# motor.net
KiCad netlist of a schematic drawn in EAGLE
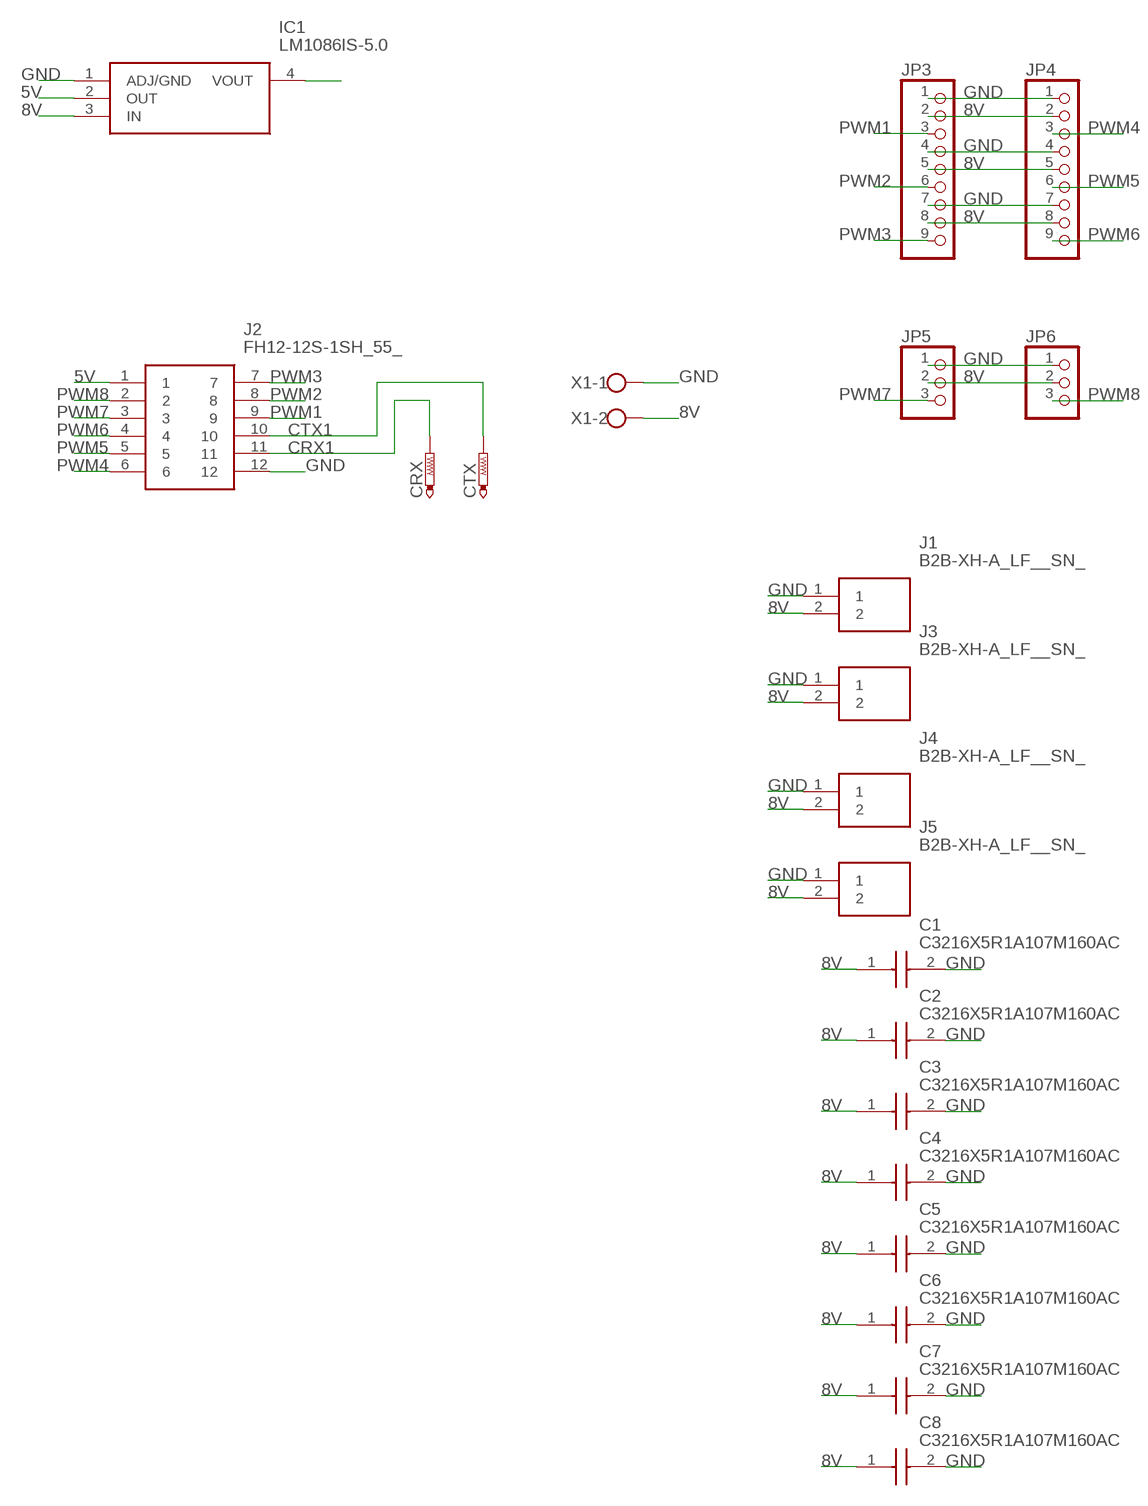
[diagram p0: schematic, sheet 1]

(export (version "E")
  (design (tool "Eeschema 10.0.6"))
  (components
    (comp (ref "C1")
      (value "C3216X5R1A107M160AC")
      (footprint "eagle-import:CAPC3216X180N")
      (fields (field (name "MOUSER_PART_NUMBER") "810-C3216X5R1A107M"))
      (libsource (lib "eagle-import") (part "C3216X5R1A107M160AC"))
    )
    (comp (ref "C2")
      (value "C3216X5R1A107M160AC")
      (footprint "eagle-import:CAPC3216X180N")
      (fields (field (name "MOUSER_PART_NUMBER") "810-C3216X5R1A107M"))
      (libsource (lib "eagle-import") (part "C3216X5R1A107M160AC"))
    )
    (comp (ref "C3")
      (value "C3216X5R1A107M160AC")
      (footprint "eagle-import:CAPC3216X180N")
      (fields (field (name "MOUSER_PART_NUMBER") "810-C3216X5R1A107M"))
      (libsource (lib "eagle-import") (part "C3216X5R1A107M160AC"))
    )
    (comp (ref "C4")
      (value "C3216X5R1A107M160AC")
      (footprint "eagle-import:CAPC3216X180N")
      (fields (field (name "MOUSER_PART_NUMBER") "810-C3216X5R1A107M"))
      (libsource (lib "eagle-import") (part "C3216X5R1A107M160AC"))
    )
    (comp (ref "C5")
      (value "C3216X5R1A107M160AC")
      (footprint "eagle-import:CAPC3216X180N")
      (fields (field (name "MOUSER_PART_NUMBER") "810-C3216X5R1A107M"))
      (libsource (lib "eagle-import") (part "C3216X5R1A107M160AC"))
    )
    (comp (ref "C6")
      (value "C3216X5R1A107M160AC")
      (footprint "eagle-import:CAPC3216X180N")
      (fields (field (name "MOUSER_PART_NUMBER") "810-C3216X5R1A107M"))
      (libsource (lib "eagle-import") (part "C3216X5R1A107M160AC"))
    )
    (comp (ref "C7")
      (value "C3216X5R1A107M160AC")
      (footprint "eagle-import:CAPC3216X180N")
      (fields (field (name "MOUSER_PART_NUMBER") "810-C3216X5R1A107M"))
      (libsource (lib "eagle-import") (part "C3216X5R1A107M160AC"))
    )
    (comp (ref "C8")
      (value "C3216X5R1A107M160AC")
      (footprint "eagle-import:CAPC3216X180N")
      (fields (field (name "MOUSER_PART_NUMBER") "810-C3216X5R1A107M"))
      (libsource (lib "eagle-import") (part "C3216X5R1A107M160AC"))
    )
    (comp (ref "CRX")
      (value "PTR1TP20R")
      (footprint "eagle-import:TP20R")
      (libsource (lib "eagle-import") (part "PTR1TP20R"))
    )
    (comp (ref "CTX")
      (value "PTR1TP20SQ")
      (footprint "eagle-import:TP20SQ")
      (libsource (lib "eagle-import") (part "PTR1TP20SQ"))
    )
    (comp (ref "IC1")
      (value "LM1086IS-5.0")
      (footprint "eagle-import:TO254P1435X457-4N")
      (fields (field (name "MOUSER_PART_NUMBER") "926-LM1086IS-50"))
      (libsource (lib "eagle-import") (part "LM1086IS-5.0"))
    )
    (comp (ref "J1")
      (value "B2B-XH-A_LF__SN_")
      (footprint "eagle-import:SHDR2W64P0X250_1X2_740X575X700")
      (fields
        (field (name "MANUFACTURER_PART_NUMBER") "B2B-XH-A(LF)(SN)")
        (field (name "RS_PART_NUMBER") "8201554P")
      )
      (libsource (lib "eagle-import") (part "B2B-XH-A_LF__SN_"))
    )
    (comp (ref "J2")
      (value "FH12-12S-1SH_55_")
      (footprint "eagle-import:FH12-12S-1SH(55)")
      (fields
        (field (name "MANUFACTURER_PART_NUMBER") "FH12-12S-1SH(55)")
        (field (name "MOUSER_PART_NUMBER") "798-FH1212S1SH55")
      )
      (libsource (lib "eagle-import") (part "FH12-12S-1SH_55_"))
    )
    (comp (ref "J3")
      (value "B2B-XH-A_LF__SN_")
      (footprint "eagle-import:SHDR2W64P0X250_1X2_740X575X700")
      (fields
        (field (name "MANUFACTURER_PART_NUMBER") "B2B-XH-A(LF)(SN)")
        (field (name "RS_PART_NUMBER") "8201554P")
      )
      (libsource (lib "eagle-import") (part "B2B-XH-A_LF__SN_"))
    )
    (comp (ref "J4")
      (value "B2B-XH-A_LF__SN_")
      (footprint "eagle-import:SHDR2W64P0X250_1X2_740X575X700")
      (fields
        (field (name "MANUFACTURER_PART_NUMBER") "B2B-XH-A(LF)(SN)")
        (field (name "RS_PART_NUMBER") "8201554P")
      )
      (libsource (lib "eagle-import") (part "B2B-XH-A_LF__SN_"))
    )
    (comp (ref "J5")
      (value "B2B-XH-A_LF__SN_")
      (footprint "eagle-import:SHDR2W64P0X250_1X2_740X575X700")
      (fields
        (field (name "MANUFACTURER_PART_NUMBER") "B2B-XH-A(LF)(SN)")
        (field (name "RS_PART_NUMBER") "8201554P")
      )
      (libsource (lib "eagle-import") (part "B2B-XH-A_LF__SN_"))
    )
    (comp (ref "JP3")
      (value "PINHD-1X9")
      (footprint "eagle-import:1X09")
      (libsource (lib "eagle-import") (part "PINHD-1X9"))
    )
    (comp (ref "JP4")
      (value "PINHD-1X9")
      (footprint "eagle-import:1X09")
      (libsource (lib "eagle-import") (part "PINHD-1X9"))
    )
    (comp (ref "JP5")
      (value "PINHD-1X3")
      (footprint "eagle-import:1X03")
      (libsource (lib "eagle-import") (part "PINHD-1X3"))
    )
    (comp (ref "JP6")
      (value "PINHD-1X3")
      (footprint "eagle-import:1X03")
      (libsource (lib "eagle-import") (part "PINHD-1X3"))
    )
    (comp (ref "X1")
      (value "W237-102")
      (footprint "eagle-import:W237-102")
      (fields (field (name "MPN") "237-102"))
      (libsource (lib "eagle-import") (part "W237-102"))
    )
  )
  (nets
    (net (code "1") (name "/5V") (class "Default")
      (node (ref "IC1") (pin "2") (pinfunction "OUT_2") (pintype "bidirectional"))
      (node (ref "J2") (pin "1") (pinfunction "1_1") (pintype "bidirectional"))
    )
    (net (code "2") (name "/8V") (class "Default")
      (node (ref "C1") (pin "1") (pinfunction "1_1") (pintype "bidirectional"))
      (node (ref "C2") (pin "1") (pinfunction "1_1") (pintype "bidirectional"))
      (node (ref "C3") (pin "1") (pinfunction "1_1") (pintype "bidirectional"))
      (node (ref "C4") (pin "1") (pinfunction "1_1") (pintype "bidirectional"))
      (node (ref "C5") (pin "1") (pinfunction "1_1") (pintype "bidirectional"))
      (node (ref "C6") (pin "1") (pinfunction "1_1") (pintype "bidirectional"))
      (node (ref "C7") (pin "1") (pinfunction "1_1") (pintype "bidirectional"))
      (node (ref "C8") (pin "1") (pinfunction "1_1") (pintype "bidirectional"))
      (node (ref "IC1") (pin "3") (pinfunction "IN_3") (pintype "bidirectional"))
      (node (ref "J1") (pin "2") (pinfunction "2_2") (pintype "bidirectional"))
      (node (ref "J3") (pin "2") (pinfunction "2_2") (pintype "bidirectional"))
      (node (ref "J4") (pin "2") (pinfunction "2_2") (pintype "bidirectional"))
      (node (ref "J5") (pin "2") (pinfunction "2_2") (pintype "bidirectional"))
      (node (ref "JP3") (pin "2") (pinfunction "2_2") (pintype "passive"))
      (node (ref "JP3") (pin "5") (pinfunction "5_5") (pintype "passive"))
      (node (ref "JP3") (pin "8") (pinfunction "8_8") (pintype "passive"))
      (node (ref "JP4") (pin "2") (pinfunction "2_2") (pintype "passive"))
      (node (ref "JP4") (pin "5") (pinfunction "5_5") (pintype "passive"))
      (node (ref "JP4") (pin "8") (pinfunction "8_8") (pintype "passive"))
      (node (ref "JP5") (pin "2") (pinfunction "2_2") (pintype "passive"))
      (node (ref "JP6") (pin "2") (pinfunction "2_2") (pintype "passive"))
      (node (ref "X1") (pin "2") (pinfunction "KL_2") (pintype "passive"))
    )
    (net (code "3") (name "/CRX1") (class "Default")
      (node (ref "CRX") (pin "TP") (pinfunction "TP_TP") (pintype "input"))
      (node (ref "J2") (pin "11") (pinfunction "11_11") (pintype "bidirectional"))
    )
    (net (code "4") (name "/CTX1") (class "Default")
      (node (ref "CTX") (pin "TP") (pinfunction "TP_TP") (pintype "input"))
      (node (ref "J2") (pin "10") (pinfunction "10_10") (pintype "bidirectional"))
    )
    (net (code "5") (name "/GND") (class "Default")
      (node (ref "C1") (pin "2") (pinfunction "2_2") (pintype "bidirectional"))
      (node (ref "C2") (pin "2") (pinfunction "2_2") (pintype "bidirectional"))
      (node (ref "C3") (pin "2") (pinfunction "2_2") (pintype "bidirectional"))
      (node (ref "C4") (pin "2") (pinfunction "2_2") (pintype "bidirectional"))
      (node (ref "C5") (pin "2") (pinfunction "2_2") (pintype "bidirectional"))
      (node (ref "C6") (pin "2") (pinfunction "2_2") (pintype "bidirectional"))
      (node (ref "C7") (pin "2") (pinfunction "2_2") (pintype "bidirectional"))
      (node (ref "C8") (pin "2") (pinfunction "2_2") (pintype "bidirectional"))
      (node (ref "IC1") (pin "1") (pinfunction "ADJ/GND_1") (pintype "bidirectional"))
      (node (ref "J1") (pin "1") (pinfunction "1_1") (pintype "bidirectional"))
      (node (ref "J2") (pin "12") (pinfunction "12_12") (pintype "bidirectional"))
      (node (ref "J3") (pin "1") (pinfunction "1_1") (pintype "bidirectional"))
      (node (ref "J4") (pin "1") (pinfunction "1_1") (pintype "bidirectional"))
      (node (ref "J5") (pin "1") (pinfunction "1_1") (pintype "bidirectional"))
      (node (ref "JP3") (pin "1") (pinfunction "1_1") (pintype "passive"))
      (node (ref "JP3") (pin "4") (pinfunction "4_4") (pintype "passive"))
      (node (ref "JP3") (pin "7") (pinfunction "7_7") (pintype "passive"))
      (node (ref "JP4") (pin "1") (pinfunction "1_1") (pintype "passive"))
      (node (ref "JP4") (pin "4") (pinfunction "4_4") (pintype "passive"))
      (node (ref "JP4") (pin "7") (pinfunction "7_7") (pintype "passive"))
      (node (ref "JP5") (pin "1") (pinfunction "1_1") (pintype "passive"))
      (node (ref "JP6") (pin "1") (pinfunction "1_1") (pintype "passive"))
      (node (ref "X1") (pin "1") (pinfunction "KL_1") (pintype "passive"))
    )
    (net (code "6") (name "/PWM1") (class "Default")
      (node (ref "J2") (pin "9") (pinfunction "9_9") (pintype "bidirectional"))
      (node (ref "JP3") (pin "3") (pinfunction "3_3") (pintype "passive"))
    )
    (net (code "7") (name "/PWM2") (class "Default")
      (node (ref "J2") (pin "8") (pinfunction "8_8") (pintype "bidirectional"))
      (node (ref "JP3") (pin "6") (pinfunction "6_6") (pintype "passive"))
    )
    (net (code "8") (name "/PWM3") (class "Default")
      (node (ref "J2") (pin "7") (pinfunction "7_7") (pintype "bidirectional"))
      (node (ref "JP3") (pin "9") (pinfunction "9_9") (pintype "passive"))
    )
    (net (code "9") (name "/PWM4") (class "Default")
      (node (ref "J2") (pin "6") (pinfunction "6_6") (pintype "bidirectional"))
      (node (ref "JP4") (pin "3") (pinfunction "3_3") (pintype "passive"))
    )
    (net (code "10") (name "/PWM5") (class "Default")
      (node (ref "J2") (pin "5") (pinfunction "5_5") (pintype "bidirectional"))
      (node (ref "JP4") (pin "6") (pinfunction "6_6") (pintype "passive"))
    )
    (net (code "11") (name "/PWM6") (class "Default")
      (node (ref "J2") (pin "4") (pinfunction "4_4") (pintype "bidirectional"))
      (node (ref "JP4") (pin "9") (pinfunction "9_9") (pintype "passive"))
    )
    (net (code "12") (name "/PWM7") (class "Default")
      (node (ref "J2") (pin "3") (pinfunction "3_3") (pintype "bidirectional"))
      (node (ref "JP5") (pin "3") (pinfunction "3_3") (pintype "passive"))
    )
    (net (code "13") (name "/PWM8") (class "Default")
      (node (ref "J2") (pin "2") (pinfunction "2_2") (pintype "bidirectional"))
      (node (ref "JP6") (pin "3") (pinfunction "3_3") (pintype "passive"))
    )
    (net (code "14") (name "unconnected-(IC1-VOUT-Pad4)") (class "Default")
      (node (ref "IC1") (pin "4") (pinfunction "VOUT_4") (pintype "bidirectional"))
    )
  )
)
